# Qwiic_Weather.net
KiCad netlist of a schematic drawn in EAGLE
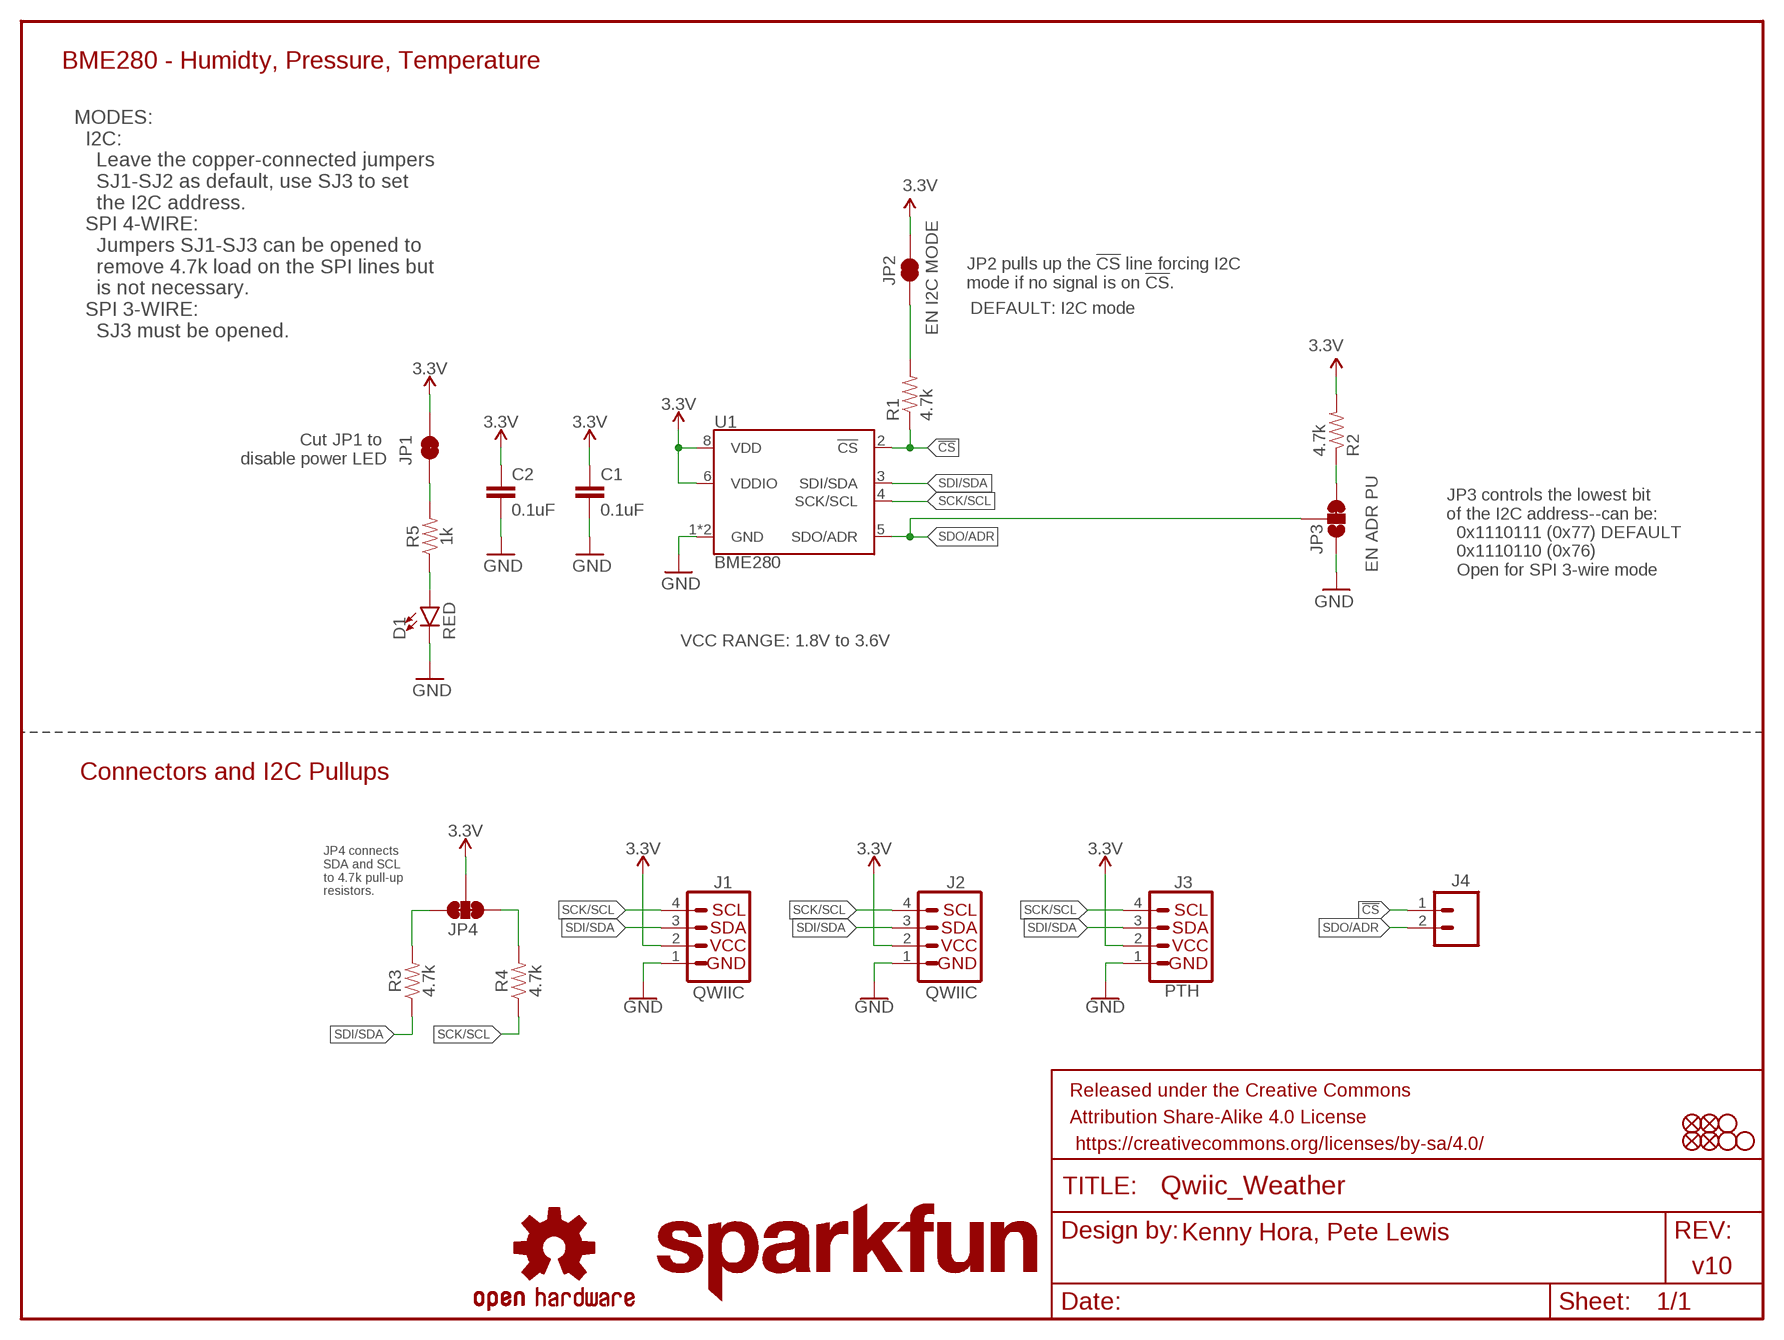
[diagram p0: schematic, sheet 1]

(export (version "E")
  (design (tool "Eeschema 10.0.6"))
  (components
    (comp (ref "C1")
      (value "0.1uF")
      (footprint "eagle-import:0603")
      (libsource (lib "eagle-import") (part "0.1UF-0603-25V-(+80/-20%)"))
    )
    (comp (ref "C2")
      (value "0.1uF")
      (footprint "eagle-import:0603")
      (libsource (lib "eagle-import") (part "0.1UF-0603-25V-(+80/-20%)"))
    )
    (comp (ref "D1")
      (value "RED")
      (footprint "eagle-import:LED-0603")
      (libsource (lib "eagle-import") (part "LED-RED0603"))
    )
    (comp (ref "FD1")
      (value "FIDUCIAL1X2")
      (footprint "eagle-import:FIDUCIAL-1X2")
      (libsource (lib "eagle-import") (part "FIDUCIAL1X2"))
    )
    (comp (ref "FD2")
      (value "FIDUCIAL1X2")
      (footprint "eagle-import:FIDUCIAL-1X2")
      (libsource (lib "eagle-import") (part "FIDUCIAL1X2"))
    )
    (comp (ref "FD3")
      (value "FIDUCIAL1X2")
      (footprint "eagle-import:FIDUCIAL-1X2")
      (libsource (lib "eagle-import") (part "FIDUCIAL1X2"))
    )
    (comp (ref "FD4")
      (value "FIDUCIAL1X2")
      (footprint "eagle-import:FIDUCIAL-1X2")
      (libsource (lib "eagle-import") (part "FIDUCIAL1X2"))
    )
    (comp (ref "FRAME1")
      (value "FRAME-LETTER")
      (footprint "eagle-import:CREATIVE_COMMONS")
      (libsource (lib "eagle-import") (part "FRAME-LETTER"))
    )
    (comp (ref "H1")
      (value "STAND-OFF")
      (footprint "eagle-import:STAND-OFF")
      (libsource (lib "eagle-import") (part "STAND-OFF"))
    )
    (comp (ref "H2")
      (value "STAND-OFF")
      (footprint "eagle-import:STAND-OFF")
      (libsource (lib "eagle-import") (part "STAND-OFF"))
    )
    (comp (ref "H4")
      (value "STAND-OFF")
      (footprint "eagle-import:STAND-OFF")
      (libsource (lib "eagle-import") (part "STAND-OFF"))
    )
    (comp (ref "J1")
      (value "QWIIC")
      (footprint "eagle-import:JST04_1MM_RA")
      (libsource (lib "eagle-import") (part "I2C_STANDARDQWIIC"))
    )
    (comp (ref "J2")
      (value "QWIIC")
      (footprint "eagle-import:JST04_1MM_RA")
      (libsource (lib "eagle-import") (part "I2C_STANDARDQWIIC"))
    )
    (comp (ref "J3")
      (value "PTH")
      (footprint "eagle-import:1X04_NO_SILK")
      (libsource (lib "eagle-import") (part "I2C_STANDARD_NO_SILK"))
    )
    (comp (ref "J4")
      (value "CONN_021X02_NO_SILK")
      (footprint "eagle-import:1X02_NO_SILK")
      (libsource (lib "eagle-import") (part "CONN_021X02_NO_SILK"))
    )
    (comp (ref "JP1")
      (value "JUMPER-SMT_2_NC_TRACE_NO-SILK")
      (footprint "eagle-import:SMT-JUMPER_2_NC_TRACE_NO-SILK")
      (libsource (lib "eagle-import") (part "JUMPER-SMT_2_NC_TRACE_NO-SILK"))
    )
    (comp (ref "JP2")
      (value "EN I2C MODE")
      (footprint "eagle-import:PAD-JUMPER-2-NC_BY_TRACE_NO_SILK")
      (libsource (lib "eagle-import") (part "JUMPER-PAD-2-NC_BY_TRACENO_SILK"))
    )
    (comp (ref "JP3")
      (value "EN ADR PU")
      (footprint "eagle-import:SMT-JUMPER_3_1-NC_TRACE_NO-SILK")
      (libsource (lib "eagle-import") (part "JUMPER-SMT_3_1-NC_TRACE_NO-SILK"))
    )
    (comp (ref "JP4")
      (value "JUMPER-SMT_3_2-NC_TRACE_NO-SILK")
      (footprint "eagle-import:SMT-JUMPER_3_2-NC_TRACE_NO-SILK")
      (libsource (lib "eagle-import") (part "JUMPER-SMT_3_2-NC_TRACE_NO-SILK"))
    )
    (comp (ref "LOGO1")
      (value "SFE_LOGO_NAME.1_INCH")
      (footprint "eagle-import:SFE_LOGO_NAME_.1")
      (libsource (lib "eagle-import") (part "SFE_LOGO_NAME.1_INCH"))
    )
    (comp (ref "LOGO4")
      (value "OSHW-LOGOS")
      (footprint "eagle-import:OSHW-LOGO-S")
      (libsource (lib "eagle-import") (part "OSHW-LOGOS"))
    )
    (comp (ref "R1")
      (value "4.7k")
      (footprint "eagle-import:0603")
      (libsource (lib "eagle-import") (part "4.7KOHM-0603-1/10W-1%"))
    )
    (comp (ref "R2")
      (value "4.7k")
      (footprint "eagle-import:0603")
      (libsource (lib "eagle-import") (part "4.7KOHM-0603-1/10W-1%"))
    )
    (comp (ref "R3")
      (value "4.7k")
      (footprint "eagle-import:0603")
      (libsource (lib "eagle-import") (part "4.7KOHM-0603-1/10W-1%"))
    )
    (comp (ref "R4")
      (value "4.7k")
      (footprint "eagle-import:0603")
      (libsource (lib "eagle-import") (part "4.7KOHM-0603-1/10W-1%"))
    )
    (comp (ref "R5")
      (value "1k")
      (footprint "eagle-import:0603")
      (libsource (lib "eagle-import") (part "1KOHM-0603-1/10W-1%"))
    )
    (comp (ref "U1")
      (value "BME280")
      (footprint "eagle-import:LGA-8-2.5X2.5")
      (libsource (lib "eagle-import") (part "BME280"))
    )
  )
  (nets
    (net (code "1") (name "/~{CS}") (class "Default")
      (node (ref "J4") (pin "1") (pinfunction "1_1") (pintype "passive"))
      (node (ref "R1") (pin "1") (pinfunction "1_1") (pintype "passive"))
      (node (ref "U1") (pin "2") (pinfunction "~{CS}_2") (pintype "bidirectional"))
    )
    (net (code "2") (name "3.3V") (class "Default")
      (node (ref "C1") (pin "1") (pinfunction "1_1") (pintype "passive"))
      (node (ref "C2") (pin "1") (pinfunction "1_1") (pintype "passive"))
      (node (ref "J1") (pin "2") (pinfunction "2_2") (pintype "power_in"))
      (node (ref "J2") (pin "2") (pinfunction "2_2") (pintype "power_in"))
      (node (ref "J3") (pin "2") (pinfunction "2_2") (pintype "power_in"))
      (node (ref "JP1") (pin "2") (pinfunction "2_2") (pintype "passive"))
      (node (ref "JP2") (pin "2") (pinfunction "2_2") (pintype "passive"))
      (node (ref "JP4") (pin "2") (pinfunction "2_2") (pintype "passive"))
      (node (ref "R2") (pin "2") (pinfunction "2_2") (pintype "passive"))
      (node (ref "U1") (pin "6") (pinfunction "VDDIO_6") (pintype "bidirectional"))
      (node (ref "U1") (pin "8") (pinfunction "VDD_8") (pintype "bidirectional"))
    )
    (net (code "3") (name "GND") (class "Default")
      (node (ref "C1") (pin "2") (pinfunction "2_2") (pintype "passive"))
      (node (ref "C2") (pin "2") (pinfunction "2_2") (pintype "passive"))
      (node (ref "D1") (pin "C") (pinfunction "C_C") (pintype "passive"))
      (node (ref "J1") (pin "1") (pinfunction "1_1") (pintype "power_in"))
      (node (ref "J2") (pin "1") (pinfunction "1_1") (pintype "power_in"))
      (node (ref "J3") (pin "1") (pinfunction "1_1") (pintype "power_in"))
      (node (ref "JP3") (pin "1") (pinfunction "1_1") (pintype "passive"))
      (node (ref "U1") (pin "1") (pinfunction "GND_1") (pintype "bidirectional"))
      (node (ref "U1") (pin "7") (pinfunction "GND_7") (pintype "bidirectional"))
    )
    (net (code "4") (name "Net-(D1-PadA)") (class "Default")
      (node (ref "D1") (pin "A") (pinfunction "A_A") (pintype "passive"))
      (node (ref "R5") (pin "1") (pinfunction "1_1") (pintype "passive"))
    )
    (net (code "5") (name "Net-(JP1-Pad1)") (class "Default")
      (node (ref "JP1") (pin "1") (pinfunction "1_1") (pintype "passive"))
      (node (ref "R5") (pin "2") (pinfunction "2_2") (pintype "passive"))
    )
    (net (code "6") (name "Net-(JP2-Pad1)") (class "Default")
      (node (ref "JP2") (pin "1") (pinfunction "1_1") (pintype "passive"))
      (node (ref "R1") (pin "2") (pinfunction "2_2") (pintype "passive"))
    )
    (net (code "7") (name "Net-(JP3-Pad3)") (class "Default")
      (node (ref "JP3") (pin "3") (pinfunction "3_3") (pintype "passive"))
      (node (ref "R2") (pin "1") (pinfunction "1_1") (pintype "passive"))
    )
    (net (code "8") (name "Net-(JP4-Pad1)") (class "Default")
      (node (ref "JP4") (pin "1") (pinfunction "1_1") (pintype "passive"))
      (node (ref "R4") (pin "2") (pinfunction "2_2") (pintype "passive"))
    )
    (net (code "9") (name "Net-(JP4-Pad3)") (class "Default")
      (node (ref "JP4") (pin "3") (pinfunction "3_3") (pintype "passive"))
      (node (ref "R3") (pin "2") (pinfunction "2_2") (pintype "passive"))
    )
    (net (code "10") (name "SCK{slash}SCL") (class "Default")
      (node (ref "J1") (pin "4") (pinfunction "4_4") (pintype "passive"))
      (node (ref "J2") (pin "4") (pinfunction "4_4") (pintype "passive"))
      (node (ref "J3") (pin "4") (pinfunction "4_4") (pintype "passive"))
      (node (ref "R4") (pin "1") (pinfunction "1_1") (pintype "passive"))
      (node (ref "U1") (pin "4") (pinfunction "SCK/SCL_4") (pintype "bidirectional"))
    )
    (net (code "11") (name "SDI{slash}SDA") (class "Default")
      (node (ref "J1") (pin "3") (pinfunction "3_3") (pintype "passive"))
      (node (ref "J2") (pin "3") (pinfunction "3_3") (pintype "passive"))
      (node (ref "J3") (pin "3") (pinfunction "3_3") (pintype "passive"))
      (node (ref "R3") (pin "1") (pinfunction "1_1") (pintype "passive"))
      (node (ref "U1") (pin "3") (pinfunction "SDI/SDA_3") (pintype "bidirectional"))
    )
    (net (code "12") (name "SDO{slash}ADR") (class "Default")
      (node (ref "J4") (pin "2") (pinfunction "2_2") (pintype "passive"))
      (node (ref "JP3") (pin "2") (pinfunction "2_2") (pintype "passive"))
      (node (ref "U1") (pin "5") (pinfunction "SDO/ADR_5") (pintype "bidirectional"))
    )
  )
)
